# matrixkeypad.net
KiCad netlist of a schematic drawn in Altium Designer
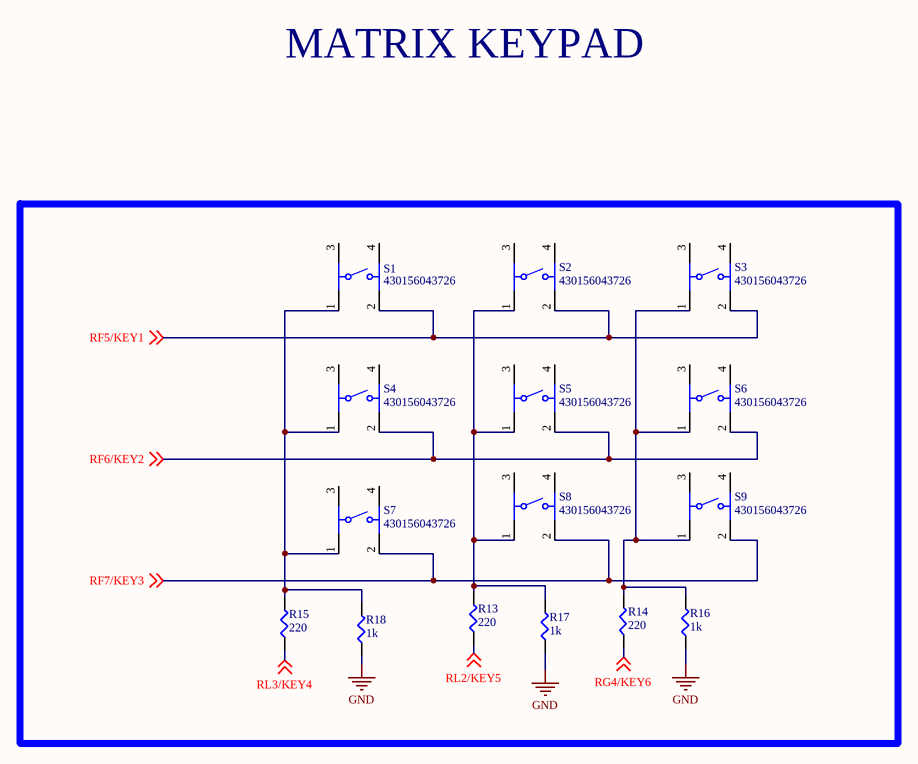
[diagram p0: matrixkeypad.SchDoc]

(export (version "E")
  (design (tool "Eeschema 10.0.6"))
  (components
    (comp (ref "R13")
      (value "220")
      (footprint "SMD-0805-RES")
      (description "RES SMD 220 OHM 1% 1/8W 0805")
      (fields (field (name "PART NUMBER") "ERJ-6ENF2200V") (field (name "DIGI-KEY PART NUMBER") "P220CCT-ND"))
      (libsource (lib "Panasonic_ERJ_0805") (part "ERJ-6ENF2200V"))
    )
    (comp (ref "R14")
      (value "220")
      (footprint "SMD-0805-RES")
      (description "RES SMD 220 OHM 1% 1/8W 0805")
      (fields (field (name "PART NUMBER") "ERJ-6ENF2200V") (field (name "DIGI-KEY PART NUMBER") "P220CCT-ND"))
      (libsource (lib "Panasonic_ERJ_0805") (part "ERJ-6ENF2200V"))
    )
    (comp (ref "R15")
      (value "220")
      (footprint "SMD-0805-RES")
      (description "RES SMD 220 OHM 1% 1/8W 0805")
      (fields (field (name "PART NUMBER") "ERJ-6ENF2200V") (field (name "DIGI-KEY PART NUMBER") "P220CCT-ND"))
      (libsource (lib "Panasonic_ERJ_0805") (part "ERJ-6ENF2200V"))
    )
    (comp (ref "R16")
      (value "1k")
      (footprint "SMD-0805-RES")
      (description "RES SMD 1K OHM 1% 1/8W 0805")
      (fields
        (field (name "PART NUMBER") "ERJ-6ENF1001V")
        (field (name "DIGI-KEY PART NUMBER") "P1.00KCCT-ND")
      )
      (libsource (lib "Panasonic_ERJ_0805") (part "ERJ-6ENF1001V"))
    )
    (comp (ref "R17")
      (value "1k")
      (footprint "SMD-0805-RES")
      (description "RES SMD 1K OHM 1% 1/8W 0805")
      (fields
        (field (name "PART NUMBER") "ERJ-6ENF1001V")
        (field (name "DIGI-KEY PART NUMBER") "P1.00KCCT-ND")
      )
      (libsource (lib "Panasonic_ERJ_0805") (part "ERJ-6ENF1001V"))
    )
    (comp (ref "R18")
      (value "1k")
      (footprint "SMD-0805-RES")
      (description "RES SMD 1K OHM 1% 1/8W 0805")
      (fields
        (field (name "PART NUMBER") "ERJ-6ENF1001V")
        (field (name "DIGI-KEY PART NUMBER") "P1.00KCCT-ND")
      )
      (libsource (lib "Panasonic_ERJ_0805") (part "ERJ-6ENF1001V"))
    )
    (comp (ref "S1")
      (value "430156043726")
      (footprint "4301x60437x6")
      (description "WS-TATV THT Tact Switch 6x6mm, height 4.3mm, 260gf")
      (fields (field (name "PUBLISHER") "Wurth Elektronik"))
      (libsource (lib "Push buttons through hole_Altium_WS-TATV_rev19a") (part "430156043726"))
    )
    (comp (ref "S2")
      (value "430156043726")
      (footprint "4301x60437x6")
      (description "WS-TATV THT Tact Switch 6x6mm, height 4.3mm, 260gf")
      (fields (field (name "PUBLISHER") "Wurth Elektronik"))
      (libsource (lib "Push buttons through hole_Altium_WS-TATV_rev19a") (part "430156043726"))
    )
    (comp (ref "S3")
      (value "430156043726")
      (footprint "4301x60437x6")
      (description "WS-TATV THT Tact Switch 6x6mm, height 4.3mm, 260gf")
      (fields (field (name "PUBLISHER") "Wurth Elektronik"))
      (libsource (lib "Push buttons through hole_Altium_WS-TATV_rev19a") (part "430156043726"))
    )
    (comp (ref "S4")
      (value "430156043726")
      (footprint "4301x60437x6")
      (description "WS-TATV THT Tact Switch 6x6mm, height 4.3mm, 260gf")
      (fields (field (name "PUBLISHER") "Wurth Elektronik"))
      (libsource (lib "Push buttons through hole_Altium_WS-TATV_rev19a") (part "430156043726"))
    )
    (comp (ref "S5")
      (value "430156043726")
      (footprint "4301x60437x6")
      (description "WS-TATV THT Tact Switch 6x6mm, height 4.3mm, 260gf")
      (fields (field (name "PUBLISHER") "Wurth Elektronik"))
      (libsource (lib "Push buttons through hole_Altium_WS-TATV_rev19a") (part "430156043726"))
    )
    (comp (ref "S6")
      (value "430156043726")
      (footprint "4301x60437x6")
      (description "WS-TATV THT Tact Switch 6x6mm, height 4.3mm, 260gf")
      (fields (field (name "PUBLISHER") "Wurth Elektronik"))
      (libsource (lib "Push buttons through hole_Altium_WS-TATV_rev19a") (part "430156043726"))
    )
    (comp (ref "S7")
      (value "430156043726")
      (footprint "4301x60437x6")
      (description "WS-TATV THT Tact Switch 6x6mm, height 4.3mm, 260gf")
      (fields (field (name "PUBLISHER") "Wurth Elektronik"))
      (libsource (lib "Push buttons through hole_Altium_WS-TATV_rev19a") (part "430156043726"))
    )
    (comp (ref "S8")
      (value "430156043726")
      (footprint "4301x60437x6")
      (description "WS-TATV THT Tact Switch 6x6mm, height 4.3mm, 260gf")
      (fields (field (name "PUBLISHER") "Wurth Elektronik"))
      (libsource (lib "Push buttons through hole_Altium_WS-TATV_rev19a") (part "430156043726"))
    )
    (comp (ref "S9")
      (value "430156043726")
      (footprint "4301x60437x6")
      (description "WS-TATV THT Tact Switch 6x6mm, height 4.3mm, 260gf")
      (fields (field (name "PUBLISHER") "Wurth Elektronik"))
      (libsource (lib "Push buttons through hole_Altium_WS-TATV_rev19a") (part "430156043726"))
    )
  )
  (nets
    (net (code "1") (name "GND") (class "Default")
      (node (ref "R16") (pin "1") (pinfunction "1_1") (pintype "passive"))
      (node (ref "R17") (pin "1") (pinfunction "1_1") (pintype "passive"))
      (node (ref "R18") (pin "1") (pinfunction "1_1") (pintype "passive"))
    )
    (net (code "2") (name "Net-(R13-Pad2)") (class "Default")
      (node (ref "R13") (pin "2") (pinfunction "2_2") (pintype "passive"))
      (node (ref "R17") (pin "2") (pinfunction "2_2") (pintype "passive"))
      (node (ref "S2") (pin "1") (pinfunction "1_1") (pintype "passive"))
      (node (ref "S5") (pin "1") (pinfunction "1_1") (pintype "passive"))
      (node (ref "S8") (pin "1") (pinfunction "1_1") (pintype "passive"))
    )
    (net (code "3") (name "Net-(R14-Pad2)") (class "Default")
      (node (ref "R14") (pin "2") (pinfunction "2_2") (pintype "passive"))
      (node (ref "R16") (pin "2") (pinfunction "2_2") (pintype "passive"))
      (node (ref "S3") (pin "1") (pinfunction "1_1") (pintype "passive"))
      (node (ref "S6") (pin "1") (pinfunction "1_1") (pintype "passive"))
      (node (ref "S9") (pin "1") (pinfunction "1_1") (pintype "passive"))
    )
    (net (code "4") (name "Net-(R15-Pad2)") (class "Default")
      (node (ref "R15") (pin "2") (pinfunction "2_2") (pintype "passive"))
      (node (ref "R18") (pin "2") (pinfunction "2_2") (pintype "passive"))
      (node (ref "S1") (pin "1") (pinfunction "1_1") (pintype "passive"))
      (node (ref "S4") (pin "1") (pinfunction "1_1") (pintype "passive"))
      (node (ref "S7") (pin "1") (pinfunction "1_1") (pintype "passive"))
    )
    (net (code "5") (name "RF5{slash}KEY1") (class "Default")
      (node (ref "S1") (pin "2") (pinfunction "2_2") (pintype "passive"))
      (node (ref "S2") (pin "2") (pinfunction "2_2") (pintype "passive"))
      (node (ref "S3") (pin "2") (pinfunction "2_2") (pintype "passive"))
    )
    (net (code "6") (name "RF6{slash}KEY2") (class "Default")
      (node (ref "S4") (pin "2") (pinfunction "2_2") (pintype "passive"))
      (node (ref "S5") (pin "2") (pinfunction "2_2") (pintype "passive"))
      (node (ref "S6") (pin "2") (pinfunction "2_2") (pintype "passive"))
    )
    (net (code "7") (name "RF7{slash}KEY3") (class "Default")
      (node (ref "S7") (pin "2") (pinfunction "2_2") (pintype "passive"))
      (node (ref "S8") (pin "2") (pinfunction "2_2") (pintype "passive"))
      (node (ref "S9") (pin "2") (pinfunction "2_2") (pintype "passive"))
    )
    (net (code "8") (name "RG4{slash}KEY6") (class "Default")
      (node (ref "R14") (pin "1") (pinfunction "1_1") (pintype "passive"))
    )
    (net (code "9") (name "RL2{slash}KEY5") (class "Default")
      (node (ref "R13") (pin "1") (pinfunction "1_1") (pintype "passive"))
    )
    (net (code "10") (name "RL3{slash}KEY4") (class "Default")
      (node (ref "R15") (pin "1") (pinfunction "1_1") (pintype "passive"))
    )
    (net (code "11") (name "unconnected-(S1-Pad3)") (class "Default")
      (node (ref "S1") (pin "3") (pinfunction "3_3") (pintype "passive"))
    )
    (net (code "12") (name "unconnected-(S1-Pad4)") (class "Default")
      (node (ref "S1") (pin "4") (pinfunction "4_4") (pintype "passive"))
    )
    (net (code "13") (name "unconnected-(S2-Pad3)") (class "Default")
      (node (ref "S2") (pin "3") (pinfunction "3_3") (pintype "passive"))
    )
    (net (code "14") (name "unconnected-(S2-Pad4)") (class "Default")
      (node (ref "S2") (pin "4") (pinfunction "4_4") (pintype "passive"))
    )
    (net (code "15") (name "unconnected-(S3-Pad3)") (class "Default")
      (node (ref "S3") (pin "3") (pinfunction "3_3") (pintype "passive"))
    )
    (net (code "16") (name "unconnected-(S3-Pad4)") (class "Default")
      (node (ref "S3") (pin "4") (pinfunction "4_4") (pintype "passive"))
    )
    (net (code "17") (name "unconnected-(S4-Pad3)") (class "Default")
      (node (ref "S4") (pin "3") (pinfunction "3_3") (pintype "passive"))
    )
    (net (code "18") (name "unconnected-(S4-Pad4)") (class "Default")
      (node (ref "S4") (pin "4") (pinfunction "4_4") (pintype "passive"))
    )
    (net (code "19") (name "unconnected-(S5-Pad3)") (class "Default")
      (node (ref "S5") (pin "3") (pinfunction "3_3") (pintype "passive"))
    )
    (net (code "20") (name "unconnected-(S5-Pad4)") (class "Default")
      (node (ref "S5") (pin "4") (pinfunction "4_4") (pintype "passive"))
    )
    (net (code "21") (name "unconnected-(S6-Pad3)") (class "Default")
      (node (ref "S6") (pin "3") (pinfunction "3_3") (pintype "passive"))
    )
    (net (code "22") (name "unconnected-(S6-Pad4)") (class "Default")
      (node (ref "S6") (pin "4") (pinfunction "4_4") (pintype "passive"))
    )
    (net (code "23") (name "unconnected-(S7-Pad3)") (class "Default")
      (node (ref "S7") (pin "3") (pinfunction "3_3") (pintype "passive"))
    )
    (net (code "24") (name "unconnected-(S7-Pad4)") (class "Default")
      (node (ref "S7") (pin "4") (pinfunction "4_4") (pintype "passive"))
    )
    (net (code "25") (name "unconnected-(S8-Pad3)") (class "Default")
      (node (ref "S8") (pin "3") (pinfunction "3_3") (pintype "passive"))
    )
    (net (code "26") (name "unconnected-(S8-Pad4)") (class "Default")
      (node (ref "S8") (pin "4") (pinfunction "4_4") (pintype "passive"))
    )
    (net (code "27") (name "unconnected-(S9-Pad3)") (class "Default")
      (node (ref "S9") (pin "3") (pinfunction "3_3") (pintype "passive"))
    )
    (net (code "28") (name "unconnected-(S9-Pad4)") (class "Default")
      (node (ref "S9") (pin "4") (pinfunction "4_4") (pintype "passive"))
    )
  )
)
